# 04_-_Camera_Interface.net
KiCad netlist of a schematic drawn in Altium Designer
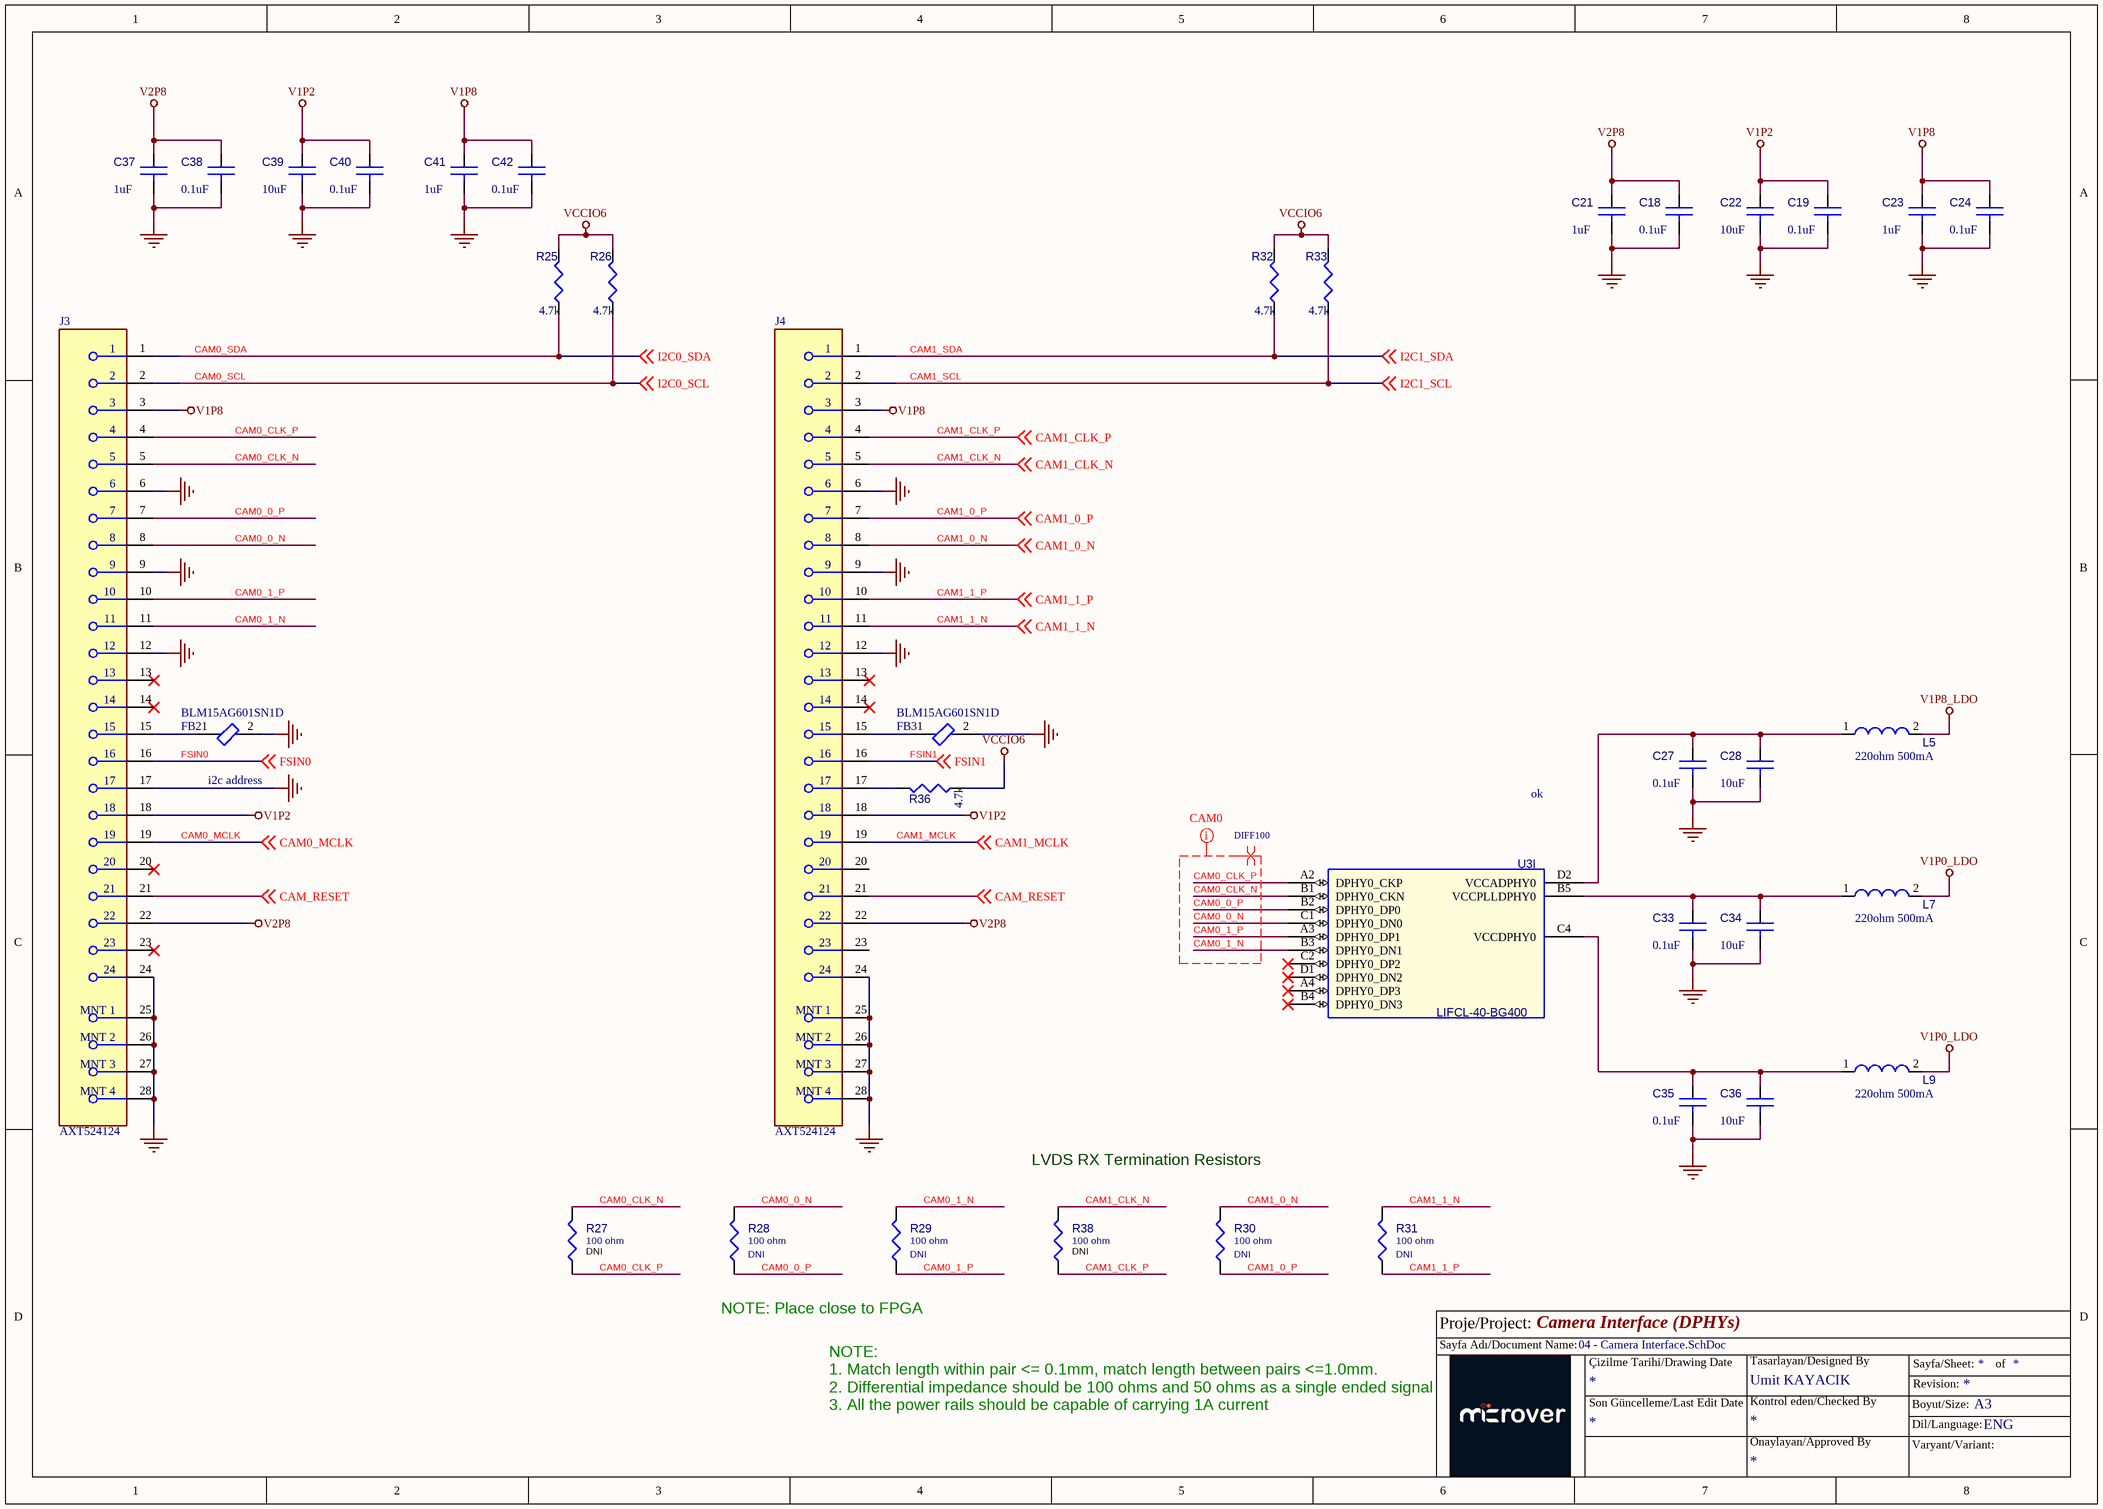
[diagram p0: 04 - Camera Interface.SchDoc]

(export (version "E")
  (design (tool "Eeschema 10.0.6"))
  (components
    (comp (ref "C18")
      (value "0.1uF")
      (footprint "C0201")
      (description "CAP CER 0.1UF 25V 10% X5R 0201")
      (fields
        (field (name "MANUFACTURER") "Murata")
        (field (name "MANUFACTURER PART NUMBER") "GRM033R61E104KE14J")
      )
      (libsource (lib "*") (part "0u1_0402"))
    )
    (comp (ref "C19")
      (value "0.1uF")
      (footprint "C0201")
      (description "CAP CER 0.1UF 25V 10% X5R 0201")
      (fields
        (field (name "MANUFACTURER") "Murata")
        (field (name "MANUFACTURER PART NUMBER") "GRM033R61E104KE14J")
      )
      (libsource (lib "*") (part "0u1_0402"))
    )
    (comp (ref "C21")
      (value "1uF")
      (footprint "C0603")
      (description "CAP CECAP CER 10UF 10V X5R 20% 0603")
      (fields
        (field (name "MANUFACTURER") "Taiyo Yuden")
        (field (name "MANUFACTURER PART NUMBER") "LMK107BJ106MALTD")
      )
      (libsource (lib "*") (part "10uF_0603"))
    )
    (comp (ref "C22")
      (value "10uF")
      (footprint "C0603")
      (description "CAP CECAP CER 10UF 10V X5R 20% 0603")
      (fields
        (field (name "MANUFACTURER") "Taiyo Yuden")
        (field (name "MANUFACTURER PART NUMBER") "LMK107BJ106MALTD")
      )
      (libsource (lib "*") (part "10uF_0603"))
    )
    (comp (ref "C23")
      (value "1uF")
      (footprint "C0603")
      (description "CAP CECAP CER 10UF 10V X5R 20% 0603")
      (fields
        (field (name "MANUFACTURER") "Taiyo Yuden")
        (field (name "MANUFACTURER PART NUMBER") "LMK107BJ106MALTD")
      )
      (libsource (lib "*") (part "10uF_0603"))
    )
    (comp (ref "C24")
      (value "0.1uF")
      (footprint "C0201")
      (description "CAP CER 0.1UF 25V 10% X5R 0201")
      (fields
        (field (name "MANUFACTURER") "Murata")
        (field (name "MANUFACTURER PART NUMBER") "GRM033R61E104KE14J")
      )
      (libsource (lib "*") (part "0u1_0402"))
    )
    (comp (ref "C27")
      (value "0.1uF")
      (footprint "C0201")
      (description "CAP CER 0.1UF 25V 10% X5R 0201")
      (fields
        (field (name "MANUFACTURER") "Murata")
        (field (name "MANUFACTURER PART NUMBER") "GRM033R61E104KE14J")
      )
      (libsource (lib "*") (part "0u1_0402"))
    )
    (comp (ref "C28")
      (value "10uF")
      (footprint "C0402")
      (description "CAP CER 10UF 10V X5R 0402")
      (fields
        (field (name "MANUFACTURER") "Samsung")
        (field (name "MANUFACTURER PART NUMBER") "CL05A106MP8NUB8")
      )
      (libsource (lib "*") (part "10uF_0603"))
    )
    (comp (ref "C33")
      (value "0.1uF")
      (footprint "C0201")
      (description "CAP CER 0.1UF 25V 10% X5R 0201")
      (fields
        (field (name "MANUFACTURER") "Murata")
        (field (name "MANUFACTURER PART NUMBER") "GRM033R61E104KE14J")
      )
      (libsource (lib "*") (part "0u1_0402"))
    )
    (comp (ref "C34")
      (value "10uF")
      (footprint "C0402")
      (description "CAP CER 10UF 10V X5R 0402")
      (fields
        (field (name "MANUFACTURER") "Samsung")
        (field (name "MANUFACTURER PART NUMBER") "CL05A106MP8NUB8")
      )
      (libsource (lib "*") (part "10uF_0603"))
    )
    (comp (ref "C35")
      (value "0.1uF")
      (footprint "C0201")
      (description "CAP CER 0.1UF 25V 10% X5R 0201")
      (fields
        (field (name "MANUFACTURER") "Murata")
        (field (name "MANUFACTURER PART NUMBER") "GRM033R61E104KE14J")
      )
      (libsource (lib "*") (part "0u1_0402"))
    )
    (comp (ref "C36")
      (value "10uF")
      (footprint "C0402")
      (description "CAP CER 10UF 10V X5R 0402")
      (fields
        (field (name "MANUFACTURER") "Samsung")
        (field (name "MANUFACTURER PART NUMBER") "CL05A106MP8NUB8")
      )
      (libsource (lib "*") (part "10uF_0603"))
    )
    (comp (ref "C37")
      (value "1uF")
      (footprint "C0603")
      (description "CAP CECAP CER 10UF 10V X5R 20% 0603")
      (fields
        (field (name "MANUFACTURER") "Taiyo Yuden")
        (field (name "MANUFACTURER PART NUMBER") "LMK107BJ106MALTD")
      )
      (libsource (lib "*") (part "10uF_0603"))
    )
    (comp (ref "C38")
      (value "0.1uF")
      (footprint "C0201")
      (description "CAP CER 0.1UF 25V 10% X5R 0201")
      (fields
        (field (name "MANUFACTURER") "Murata")
        (field (name "MANUFACTURER PART NUMBER") "GRM033R61E104KE14J")
      )
      (libsource (lib "*") (part "0u1_0402"))
    )
    (comp (ref "C39")
      (value "10uF")
      (footprint "C0603")
      (description "CAP CECAP CER 10UF 10V X5R 20% 0603")
      (fields
        (field (name "MANUFACTURER") "Taiyo Yuden")
        (field (name "MANUFACTURER PART NUMBER") "LMK107BJ106MALTD")
      )
      (libsource (lib "*") (part "10uF_0603"))
    )
    (comp (ref "C40")
      (value "0.1uF")
      (footprint "C0201")
      (description "CAP CER 0.1UF 25V 10% X5R 0201")
      (fields
        (field (name "MANUFACTURER") "Murata")
        (field (name "MANUFACTURER PART NUMBER") "GRM033R61E104KE14J")
      )
      (libsource (lib "*") (part "0u1_0402"))
    )
    (comp (ref "C41")
      (value "1uF")
      (footprint "C0603")
      (description "CAP CECAP CER 10UF 10V X5R 20% 0603")
      (fields
        (field (name "MANUFACTURER") "Taiyo Yuden")
        (field (name "MANUFACTURER PART NUMBER") "LMK107BJ106MALTD")
      )
      (libsource (lib "*") (part "10uF_0603"))
    )
    (comp (ref "C42")
      (value "0.1uF")
      (footprint "C0201")
      (description "CAP CER 0.1UF 25V 10% X5R 0201")
      (fields
        (field (name "MANUFACTURER") "Murata")
        (field (name "MANUFACTURER PART NUMBER") "GRM033R61E104KE14J")
      )
      (libsource (lib "*") (part "0u1_0402"))
    )
    (comp (ref "FB2")
      (value "BLM15AG601SN1D")
      (footprint "FP-BLM15-0_05-MFG")
      (description "Chip Ferrite Bead, 0402, 600Ω @ 100MHz, 0.52Ω, 25%, 300mA")
      (fields (field (name "TOLERANCE") "25%"))
      (libsource (lib "Altium Content Vault") (part "5f30dd21d616792df468990f7003faa"))
    )
    (comp (ref "FB3")
      (value "BLM15AG601SN1D")
      (footprint "FP-BLM15-0_05-MFG")
      (description "Chip Ferrite Bead, 0402, 600Ω @ 100MHz, 0.52Ω, 25%, 300mA")
      (fields (field (name "TOLERANCE") "25%"))
      (libsource (lib "Altium Content Vault") (part "5f30dd21d616792df468990f7003faa"))
    )
    (comp (ref "J3")
      (value "AXT524124")
      (footprint "FP-AXT524124-MFG")
      (description "AXT524124 24 Position 0.4 mm Pitch Dual Row Board to Board Socket Narrow Pitch Connector")
      (libsource (lib "Chronos") (part "AXT524124"))
    )
    (comp (ref "J4")
      (value "AXT524124")
      (footprint "FP-AXT524124-MFG")
      (description "AXT524124 24 Position 0.4 mm Pitch Dual Row Board to Board Socket Narrow Pitch Connector")
      (libsource (lib "Chronos") (part "AXT524124"))
    )
    (comp (ref "L5")
      (value "220ohm 500mA")
      (footprint "FB0402")
      (description "FERRITE BEAD 600 OHM 0402 1LN")
      (fields
        (field (name "MANUFACTURER") "Murata")
        (field (name "MANUFACTURER PART NUMBER") "BLM15AX601SN1D")
      )
      (libsource (lib "*") (part "FB0603"))
    )
    (comp (ref "L7")
      (value "220ohm 500mA")
      (footprint "FB0402")
      (description "FERRITE BEAD 600 OHM 0402 1LN")
      (fields
        (field (name "MANUFACTURER") "Murata")
        (field (name "MANUFACTURER PART NUMBER") "BLM15AX601SN1D")
      )
      (libsource (lib "*") (part "FB0603"))
    )
    (comp (ref "L9")
      (value "220ohm 500mA")
      (footprint "FB0402")
      (description "FERRITE BEAD 600 OHM 0402 1LN")
      (fields
        (field (name "MANUFACTURER") "Murata")
        (field (name "MANUFACTURER PART NUMBER") "BLM15AX601SN1D")
      )
      (libsource (lib "*") (part "FB0603"))
    )
    (comp (ref "R25")
      (value "4.7k")
      (footprint "R0402")
      (description "RES SMD 2.2K OHM 1% 1/10W 0402")
      (fields
        (field (name "MANUFACTURER PART NUMBER") "ERJ-2RKF2201X")
        (field (name "MANUFACTURER") "Panasonic")
      )
      (libsource (lib "*") (part "5k1_0402"))
    )
    (comp (ref "R26")
      (value "4.7k")
      (footprint "R0402")
      (description "RES SMD 2.2K OHM 1% 1/10W 0402")
      (fields
        (field (name "MANUFACTURER PART NUMBER") "ERJ-2RKF2201X")
        (field (name "MANUFACTURER") "Panasonic")
      )
      (libsource (lib "*") (part "5k1_0402"))
    )
    (comp (ref "R27")
      (value "100 ohm")
      (footprint "R0201")
      (description "RES SMD 100 OHM 1% 1/20W 0201")
      (fields (field (name "MFG") "Yageo") (field (name "MANUFACTURER PART NUMBER") "RC0201FR-07100RL"))
      (libsource (lib "*") (part "RES_100K_1W16_0402_5P"))
    )
    (comp (ref "R28")
      (value "100 ohm")
      (footprint "R0201")
      (description "RES SMD 100 OHM 1% 1/20W 0201")
      (fields
        (field (name "MFG") "Yageo")
        (field (name "MANUFACTURER PART NUMBER") "RC0201FR-07100RL")
        (field (name "ASSY") "DNI")
      )
      (libsource (lib "*") (part "RES_100K_1W16_0402_5P"))
    )
    (comp (ref "R29")
      (value "100 ohm")
      (footprint "R0201")
      (description "RES SMD 100 OHM 1% 1/20W 0201")
      (fields
        (field (name "MFG") "Yageo")
        (field (name "MANUFACTURER PART NUMBER") "RC0201FR-07100RL")
        (field (name "ASSY") "DNI")
      )
      (libsource (lib "*") (part "RES_100K_1W16_0402_5P"))
    )
    (comp (ref "R30")
      (value "100 ohm")
      (footprint "R0201")
      (description "RES SMD 100 OHM 1% 1/20W 0201")
      (fields
        (field (name "MFG") "Yageo")
        (field (name "ASSY") "DNI")
        (field (name "MANUFACTURER PART NUMBER") "RC0201FR-07100RL")
      )
      (libsource (lib "*") (part "RES_100K_1W16_0402_5P"))
    )
    (comp (ref "R31")
      (value "100 ohm")
      (footprint "R0201")
      (description "RES SMD 100 OHM 1% 1/20W 0201")
      (fields
        (field (name "MFG") "Yageo")
        (field (name "ASSY") "DNI")
        (field (name "MANUFACTURER PART NUMBER") "RC0201FR-07100RL")
      )
      (libsource (lib "*") (part "RES_100K_1W16_0402_5P"))
    )
    (comp (ref "R32")
      (value "4.7k")
      (footprint "R0402")
      (description "RES SMD 2.2K OHM 1% 1/10W 0402")
      (fields
        (field (name "MANUFACTURER PART NUMBER") "ERJ-2RKF2201X")
        (field (name "MANUFACTURER") "Panasonic")
      )
      (libsource (lib "*") (part "5k1_0402"))
    )
    (comp (ref "R33")
      (value "4.7k")
      (footprint "R0402")
      (description "RES SMD 2.2K OHM 1% 1/10W 0402")
      (fields
        (field (name "MANUFACTURER PART NUMBER") "ERJ-2RKF2201X")
        (field (name "MANUFACTURER") "Panasonic")
      )
      (libsource (lib "*") (part "5k1_0402"))
    )
    (comp (ref "R36")
      (value "4.7k")
      (footprint "R0402")
      (description "RES SMD 2.2K OHM 1% 1/10W 0402")
      (fields
        (field (name "MANUFACTURER PART NUMBER") "ERJ-2RKF2201X")
        (field (name "MANUFACTURER") "Panasonic")
      )
      (libsource (lib "*") (part "5k1_0402"))
    )
    (comp (ref "R38")
      (value "100 ohm")
      (footprint "R0201")
      (description "RES SMD 100 OHM 1% 1/20W 0201")
      (fields (field (name "MFG") "Yageo") (field (name "MANUFACTURER PART NUMBER") "RC0201FR-07100RL"))
      (libsource (lib "*") (part "RES_100K_1W16_0402_5P"))
    )
    (comp (ref "U3")
      (value "LIFCL-40-BG400")
      (footprint "LIFCL-40-BG400")
      (libsource (lib "*") (part "LIFCL-40-BG400"))
    )
  )
  (nets
    (net (code "1") (name "/CAM0_0_N") (class "Default")
      (node (ref "J3") (pin "8") (pinfunction "8_8") (pintype "passive"))
      (node (ref "R28") (pin "2") (pinfunction "2_2") (pintype "passive"))
      (node (ref "U3") (pin "C1") (pinfunction "DPHY0_DN0_C1") (pintype "bidirectional"))
    )
    (net (code "2") (name "/CAM0_0_P") (class "Default")
      (node (ref "J3") (pin "7") (pinfunction "7_7") (pintype "passive"))
      (node (ref "R28") (pin "1") (pinfunction "1_1") (pintype "passive"))
      (node (ref "U3") (pin "B2") (pinfunction "DPHY0_DP0_B2") (pintype "bidirectional"))
    )
    (net (code "3") (name "/CAM0_1_N") (class "Default")
      (node (ref "J3") (pin "11") (pinfunction "11_11") (pintype "passive"))
      (node (ref "R29") (pin "2") (pinfunction "2_2") (pintype "passive"))
      (node (ref "U3") (pin "B3") (pinfunction "DPHY0_DN1_B3") (pintype "bidirectional"))
    )
    (net (code "4") (name "/CAM0_1_P") (class "Default")
      (node (ref "J3") (pin "10") (pinfunction "10_10") (pintype "passive"))
      (node (ref "R29") (pin "1") (pinfunction "1_1") (pintype "passive"))
      (node (ref "U3") (pin "A3") (pinfunction "DPHY0_DP1_A3") (pintype "bidirectional"))
    )
    (net (code "5") (name "/CAM0_CLK_N") (class "Default")
      (node (ref "J3") (pin "5") (pinfunction "5_5") (pintype "passive"))
      (node (ref "R27") (pin "2") (pinfunction "2_2") (pintype "passive"))
      (node (ref "U3") (pin "B1") (pinfunction "DPHY0_CKN_B1") (pintype "bidirectional"))
    )
    (net (code "6") (name "/CAM0_CLK_P") (class "Default")
      (node (ref "J3") (pin "4") (pinfunction "4_4") (pintype "passive"))
      (node (ref "R27") (pin "1") (pinfunction "1_1") (pintype "passive"))
      (node (ref "U3") (pin "A2") (pinfunction "DPHY0_CKP_A2") (pintype "bidirectional"))
    )
    (net (code "7") (name "CAM0_MCLK") (class "Default")
      (node (ref "J3") (pin "19") (pinfunction "19_19") (pintype "passive"))
    )
    (net (code "8") (name "CAM1_0_N") (class "Default")
      (node (ref "J4") (pin "8") (pinfunction "8_8") (pintype "passive"))
      (node (ref "R30") (pin "2") (pinfunction "2_2") (pintype "passive"))
    )
    (net (code "9") (name "CAM1_0_P") (class "Default")
      (node (ref "J4") (pin "7") (pinfunction "7_7") (pintype "passive"))
      (node (ref "R30") (pin "1") (pinfunction "1_1") (pintype "passive"))
    )
    (net (code "10") (name "CAM1_1_N") (class "Default")
      (node (ref "J4") (pin "11") (pinfunction "11_11") (pintype "passive"))
      (node (ref "R31") (pin "2") (pinfunction "2_2") (pintype "passive"))
    )
    (net (code "11") (name "CAM1_1_P") (class "Default")
      (node (ref "J4") (pin "10") (pinfunction "10_10") (pintype "passive"))
      (node (ref "R31") (pin "1") (pinfunction "1_1") (pintype "passive"))
    )
    (net (code "12") (name "CAM1_CLK_N") (class "Default")
      (node (ref "J4") (pin "5") (pinfunction "5_5") (pintype "passive"))
      (node (ref "R38") (pin "2") (pinfunction "2_2") (pintype "passive"))
    )
    (net (code "13") (name "CAM1_CLK_P") (class "Default")
      (node (ref "J4") (pin "4") (pinfunction "4_4") (pintype "passive"))
      (node (ref "R38") (pin "1") (pinfunction "1_1") (pintype "passive"))
    )
    (net (code "14") (name "CAM1_MCLK") (class "Default")
      (node (ref "J4") (pin "19") (pinfunction "19_19") (pintype "passive"))
    )
    (net (code "15") (name "CAM_RESET") (class "Default")
      (node (ref "J3") (pin "21") (pinfunction "21_21") (pintype "passive"))
      (node (ref "J4") (pin "21") (pinfunction "21_21") (pintype "passive"))
    )
    (net (code "16") (name "FSIN0") (class "Default")
      (node (ref "J3") (pin "16") (pinfunction "16_16") (pintype "passive"))
    )
    (net (code "17") (name "FSIN1") (class "Default")
      (node (ref "J4") (pin "16") (pinfunction "16_16") (pintype "passive"))
    )
    (net (code "18") (name "GND") (class "Default")
      (node (ref "C18") (pin "2") (pinfunction "2_2") (pintype "passive"))
      (node (ref "C19") (pin "2") (pinfunction "2_2") (pintype "passive"))
      (node (ref "C21") (pin "2") (pinfunction "2_2") (pintype "passive"))
      (node (ref "C22") (pin "2") (pinfunction "2_2") (pintype "passive"))
      (node (ref "C23") (pin "2") (pinfunction "2_2") (pintype "passive"))
      (node (ref "C24") (pin "2") (pinfunction "2_2") (pintype "passive"))
      (node (ref "C27") (pin "2") (pinfunction "2_2") (pintype "passive"))
      (node (ref "C28") (pin "2") (pinfunction "2_2") (pintype "passive"))
      (node (ref "C33") (pin "2") (pinfunction "2_2") (pintype "passive"))
      (node (ref "C34") (pin "2") (pinfunction "2_2") (pintype "passive"))
      (node (ref "C35") (pin "2") (pinfunction "2_2") (pintype "passive"))
      (node (ref "C36") (pin "2") (pinfunction "2_2") (pintype "passive"))
      (node (ref "C37") (pin "2") (pinfunction "2_2") (pintype "passive"))
      (node (ref "C38") (pin "2") (pinfunction "2_2") (pintype "passive"))
      (node (ref "C39") (pin "2") (pinfunction "2_2") (pintype "passive"))
      (node (ref "C40") (pin "2") (pinfunction "2_2") (pintype "passive"))
      (node (ref "C41") (pin "2") (pinfunction "2_2") (pintype "passive"))
      (node (ref "C42") (pin "2") (pinfunction "2_2") (pintype "passive"))
      (node (ref "FB2") (pin "2") (pinfunction "2_2") (pintype "passive"))
      (node (ref "FB3") (pin "2") (pinfunction "2_2") (pintype "passive"))
      (node (ref "J3") (pin "12") (pinfunction "12_12") (pintype "passive"))
      (node (ref "J3") (pin "17") (pinfunction "17_17") (pintype "passive"))
      (node (ref "J3") (pin "24") (pinfunction "24_24") (pintype "passive"))
      (node (ref "J3") (pin "25") (pinfunction "MNT_1_25") (pintype "passive"))
      (node (ref "J3") (pin "26") (pinfunction "MNT_2_26") (pintype "passive"))
      (node (ref "J3") (pin "27") (pinfunction "MNT_3_27") (pintype "passive"))
      (node (ref "J3") (pin "28") (pinfunction "MNT_4_28") (pintype "passive"))
      (node (ref "J3") (pin "6") (pinfunction "6_6") (pintype "passive"))
      (node (ref "J3") (pin "9") (pinfunction "9_9") (pintype "passive"))
      (node (ref "J4") (pin "12") (pinfunction "12_12") (pintype "passive"))
      (node (ref "J4") (pin "24") (pinfunction "24_24") (pintype "passive"))
      (node (ref "J4") (pin "25") (pinfunction "MNT_1_25") (pintype "passive"))
      (node (ref "J4") (pin "26") (pinfunction "MNT_2_26") (pintype "passive"))
      (node (ref "J4") (pin "27") (pinfunction "MNT_3_27") (pintype "passive"))
      (node (ref "J4") (pin "28") (pinfunction "MNT_4_28") (pintype "passive"))
      (node (ref "J4") (pin "6") (pinfunction "6_6") (pintype "passive"))
      (node (ref "J4") (pin "9") (pinfunction "9_9") (pintype "passive"))
    )
    (net (code "19") (name "I2C0_SCL") (class "Default")
      (node (ref "J3") (pin "2") (pinfunction "2_2") (pintype "passive"))
      (node (ref "R26") (pin "2") (pinfunction "2_2") (pintype "passive"))
    )
    (net (code "20") (name "I2C0_SDA") (class "Default")
      (node (ref "J3") (pin "1") (pinfunction "1_1") (pintype "passive"))
      (node (ref "R25") (pin "2") (pinfunction "2_2") (pintype "passive"))
    )
    (net (code "21") (name "I2C1_SCL") (class "Default")
      (node (ref "J4") (pin "2") (pinfunction "2_2") (pintype "passive"))
      (node (ref "R33") (pin "2") (pinfunction "2_2") (pintype "passive"))
    )
    (net (code "22") (name "I2C1_SDA") (class "Default")
      (node (ref "J4") (pin "1") (pinfunction "1_1") (pintype "passive"))
      (node (ref "R32") (pin "2") (pinfunction "2_2") (pintype "passive"))
    )
    (net (code "23") (name "Net-(FB2-Pad1)") (class "Default")
      (node (ref "FB2") (pin "1") (pinfunction "1_1") (pintype "passive"))
      (node (ref "J3") (pin "15") (pinfunction "15_15") (pintype "passive"))
    )
    (net (code "24") (name "Net-(FB3-Pad1)") (class "Default")
      (node (ref "FB3") (pin "1") (pinfunction "1_1") (pintype "passive"))
      (node (ref "J4") (pin "15") (pinfunction "15_15") (pintype "passive"))
    )
    (net (code "25") (name "Net-(J4-Pad17)") (class "Default")
      (node (ref "J4") (pin "17") (pinfunction "17_17") (pintype "passive"))
      (node (ref "R36") (pin "1") (pinfunction "1_1") (pintype "passive"))
    )
    (net (code "26") (name "Net-(U3I-VCCADPHY0)") (class "Default")
      (node (ref "C27") (pin "1") (pinfunction "1_1") (pintype "passive"))
      (node (ref "C28") (pin "1") (pinfunction "1_1") (pintype "passive"))
      (node (ref "L5") (pin "1") (pinfunction "1_1") (pintype "passive"))
      (node (ref "U3") (pin "D2") (pinfunction "VCCADPHY0_D2") (pintype "power_in"))
    )
    (net (code "27") (name "Net-(U3I-VCCDPHY0)") (class "Default")
      (node (ref "C35") (pin "1") (pinfunction "1_1") (pintype "passive"))
      (node (ref "C36") (pin "1") (pinfunction "1_1") (pintype "passive"))
      (node (ref "L9") (pin "1") (pinfunction "1_1") (pintype "passive"))
      (node (ref "U3") (pin "C4") (pinfunction "VCCDPHY0_C4") (pintype "power_in"))
    )
    (net (code "28") (name "Net-(U3I-VCCPLLDPHY0)") (class "Default")
      (node (ref "C33") (pin "1") (pinfunction "1_1") (pintype "passive"))
      (node (ref "C34") (pin "1") (pinfunction "1_1") (pintype "passive"))
      (node (ref "L7") (pin "1") (pinfunction "1_1") (pintype "passive"))
      (node (ref "U3") (pin "B5") (pinfunction "VCCPLLDPHY0_B5") (pintype "power_in"))
    )
    (net (code "29") (name "V1P0_LDO") (class "Default")
      (node (ref "L7") (pin "2") (pinfunction "2_2") (pintype "passive"))
      (node (ref "L9") (pin "2") (pinfunction "2_2") (pintype "passive"))
    )
    (net (code "30") (name "V1P2") (class "Default")
      (node (ref "C19") (pin "1") (pinfunction "1_1") (pintype "passive"))
      (node (ref "C22") (pin "1") (pinfunction "1_1") (pintype "passive"))
      (node (ref "C39") (pin "1") (pinfunction "1_1") (pintype "passive"))
      (node (ref "C40") (pin "1") (pinfunction "1_1") (pintype "passive"))
      (node (ref "J3") (pin "18") (pinfunction "18_18") (pintype "passive"))
      (node (ref "J4") (pin "18") (pinfunction "18_18") (pintype "passive"))
    )
    (net (code "31") (name "V1P8") (class "Default")
      (node (ref "C23") (pin "1") (pinfunction "1_1") (pintype "passive"))
      (node (ref "C24") (pin "1") (pinfunction "1_1") (pintype "passive"))
      (node (ref "C41") (pin "1") (pinfunction "1_1") (pintype "passive"))
      (node (ref "C42") (pin "1") (pinfunction "1_1") (pintype "passive"))
      (node (ref "J3") (pin "3") (pinfunction "3_3") (pintype "passive"))
      (node (ref "J4") (pin "3") (pinfunction "3_3") (pintype "passive"))
    )
    (net (code "32") (name "V1P8_LDO") (class "Default")
      (node (ref "L5") (pin "2") (pinfunction "2_2") (pintype "passive"))
    )
    (net (code "33") (name "V2P8") (class "Default")
      (node (ref "C18") (pin "1") (pinfunction "1_1") (pintype "passive"))
      (node (ref "C21") (pin "1") (pinfunction "1_1") (pintype "passive"))
      (node (ref "C37") (pin "1") (pinfunction "1_1") (pintype "passive"))
      (node (ref "C38") (pin "1") (pinfunction "1_1") (pintype "passive"))
      (node (ref "J3") (pin "22") (pinfunction "22_22") (pintype "passive"))
      (node (ref "J4") (pin "22") (pinfunction "22_22") (pintype "passive"))
    )
    (net (code "34") (name "VCCIO6") (class "Default")
      (node (ref "R25") (pin "1") (pinfunction "1_1") (pintype "passive"))
      (node (ref "R26") (pin "1") (pinfunction "1_1") (pintype "passive"))
      (node (ref "R32") (pin "1") (pinfunction "1_1") (pintype "passive"))
      (node (ref "R33") (pin "1") (pinfunction "1_1") (pintype "passive"))
      (node (ref "R36") (pin "2") (pinfunction "2_2") (pintype "passive"))
    )
    (net (code "35") (name "unconnected-(J3-Pad13)") (class "Default")
      (node (ref "J3") (pin "13") (pinfunction "13_13") (pintype "passive+no_connect"))
    )
    (net (code "36") (name "unconnected-(J3-Pad14)") (class "Default")
      (node (ref "J3") (pin "14") (pinfunction "14_14") (pintype "passive+no_connect"))
    )
    (net (code "37") (name "unconnected-(J3-Pad20)") (class "Default")
      (node (ref "J3") (pin "20") (pinfunction "20_20") (pintype "passive+no_connect"))
    )
    (net (code "38") (name "unconnected-(J3-Pad23)") (class "Default")
      (node (ref "J3") (pin "23") (pinfunction "23_23") (pintype "passive+no_connect"))
    )
    (net (code "39") (name "unconnected-(J4-Pad13)") (class "Default")
      (node (ref "J4") (pin "13") (pinfunction "13_13") (pintype "passive+no_connect"))
    )
    (net (code "40") (name "unconnected-(J4-Pad14)") (class "Default")
      (node (ref "J4") (pin "14") (pinfunction "14_14") (pintype "passive+no_connect"))
    )
    (net (code "41") (name "unconnected-(J4-Pad20)") (class "Default")
      (node (ref "J4") (pin "20") (pinfunction "20_20") (pintype "passive"))
    )
    (net (code "42") (name "unconnected-(J4-Pad23)") (class "Default")
      (node (ref "J4") (pin "23") (pinfunction "23_23") (pintype "passive"))
    )
    (net (code "43") (name "unconnected-(U3I-DPHY0_DN2-PadD1)") (class "Default")
      (node (ref "U3") (pin "D1") (pinfunction "DPHY0_DN2_D1") (pintype "bidirectional+no_connect"))
    )
    (net (code "44") (name "unconnected-(U3I-DPHY0_DN3-PadB4)") (class "Default")
      (node (ref "U3") (pin "B4") (pinfunction "DPHY0_DN3_B4") (pintype "bidirectional+no_connect"))
    )
    (net (code "45") (name "unconnected-(U3I-DPHY0_DP2-PadC2)") (class "Default")
      (node (ref "U3") (pin "C2") (pinfunction "DPHY0_DP2_C2") (pintype "bidirectional+no_connect"))
    )
    (net (code "46") (name "unconnected-(U3I-DPHY0_DP3-PadA4)") (class "Default")
      (node (ref "U3") (pin "A4") (pinfunction "DPHY0_DP3_A4") (pintype "bidirectional+no_connect"))
    )
  )
)
